# SparkFun_IoT_RedBoard-ESP32.net
KiCad netlist of a schematic drawn in EAGLE
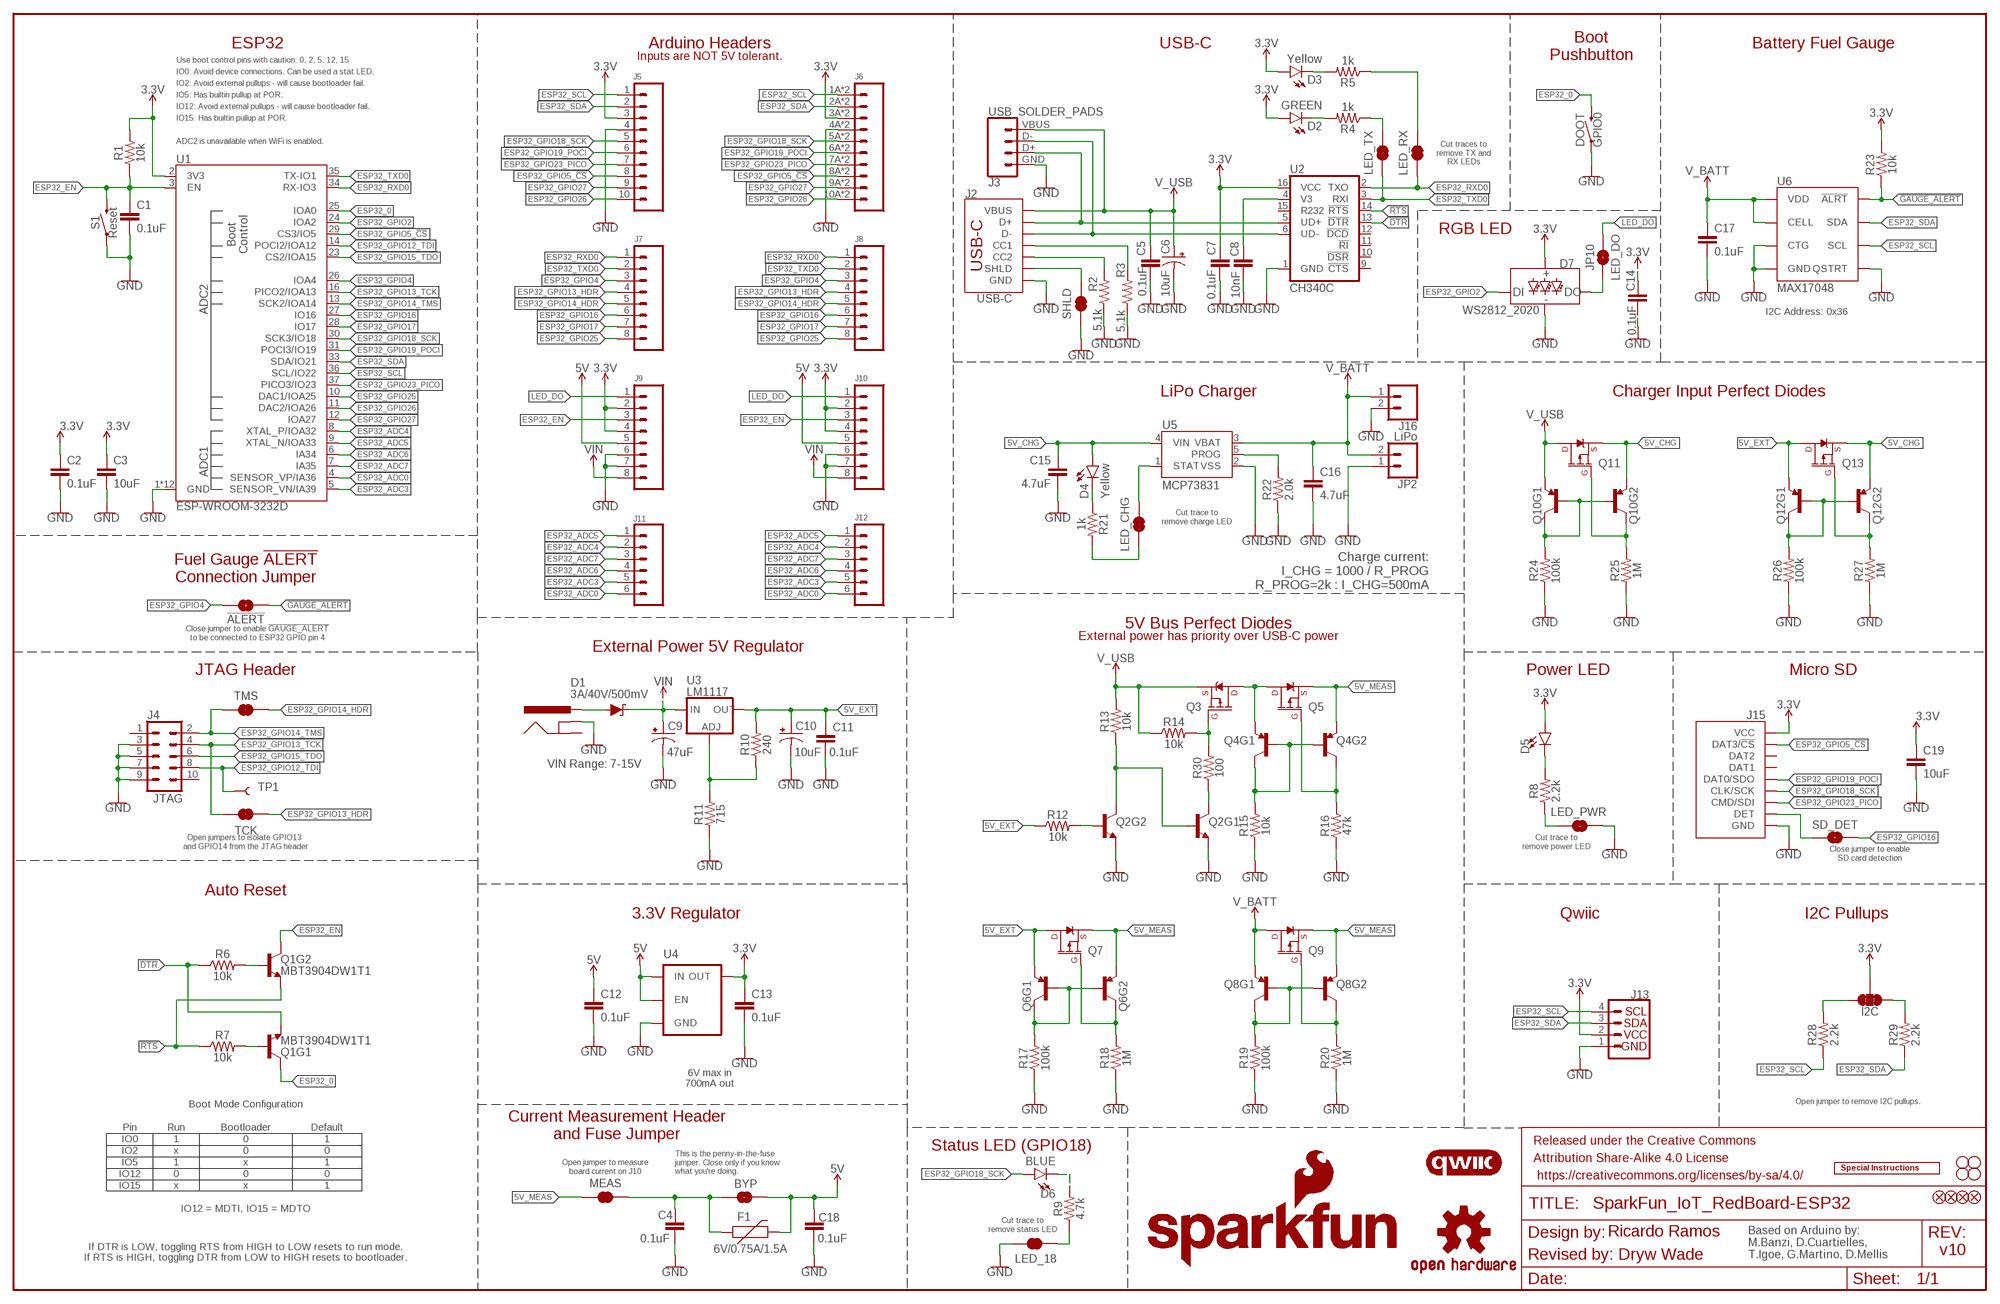
[diagram p0: schematic, sheet 1]

(export (version "E")
  (design (tool "Eeschema 10.0.6"))
  (components
    (comp (ref "!ALERT!")
      (value "JUMPER-SMT_2_NO_SILK")
      (footprint "eagle-import:SMT-JUMPER_2_NO_SILK")
      (libsource (lib "eagle-import") (part "JUMPER-SMT_2_NO_SILK"))
    )
    (comp (ref "BYP")
      (value "JUMPER-SMT_2_NO_SILK")
      (footprint "eagle-import:SMT-JUMPER_2_NO_SILK")
      (libsource (lib "eagle-import") (part "JUMPER-SMT_2_NO_SILK"))
    )
    (comp (ref "C1")
      (value "0.1uF")
      (footprint "eagle-import:0603")
      (libsource (lib "eagle-import") (part "0.1UF-0603-25V-(+80/-20%)"))
    )
    (comp (ref "C2")
      (value "0.1uF")
      (footprint "eagle-import:0603")
      (libsource (lib "eagle-import") (part "0.1UF-0603-25V-(+80/-20%)"))
    )
    (comp (ref "C3")
      (value "10uF")
      (footprint "eagle-import:0603")
      (libsource (lib "eagle-import") (part "10UF-0603-6.3V-20%"))
    )
    (comp (ref "C4")
      (value "0.1uF")
      (footprint "eagle-import:0603")
      (libsource (lib "eagle-import") (part "0.1UF-0603-25V-(+80/-20%)"))
    )
    (comp (ref "C5")
      (value "0.1uF")
      (footprint "eagle-import:0603")
      (libsource (lib "eagle-import") (part "0.1UF-0603-25V-(+80/-20%)"))
    )
    (comp (ref "C6")
      (value "10uF")
      (footprint "eagle-import:EIA3216")
      (libsource (lib "eagle-import") (part "10UF-POLAR-EIA3216-16V-10%(TANT)"))
    )
    (comp (ref "C7")
      (value "0.1uF")
      (footprint "eagle-import:0603")
      (libsource (lib "eagle-import") (part "0.1UF-0603-25V-(+80/-20%)"))
    )
    (comp (ref "C8")
      (value "10nF")
      (footprint "eagle-import:0603")
      (libsource (lib "eagle-import") (part "10NF-0603-50V-10%"))
    )
    (comp (ref "C9")
      (value "47uF")
      (footprint "eagle-import:PANASONIC_D")
      (libsource (lib "eagle-import") (part "47UF-POLAR-PANASONIC_D-35V-20%"))
    )
    (comp (ref "C10")
      (value "10uF")
      (footprint "eagle-import:EIA3216")
      (libsource (lib "eagle-import") (part "10UF-POLAR-EIA3216-16V-10%(TANT)"))
    )
    (comp (ref "C11")
      (value "0.1uF")
      (footprint "eagle-import:0603")
      (libsource (lib "eagle-import") (part "0.1UF-0603-25V-(+80/-20%)"))
    )
    (comp (ref "C12")
      (value "0.1uF")
      (footprint "eagle-import:0603")
      (libsource (lib "eagle-import") (part "0.1UF-0603-25V-(+80/-20%)"))
    )
    (comp (ref "C13")
      (value "0.1uF")
      (footprint "eagle-import:0603")
      (libsource (lib "eagle-import") (part "0.1UF-0603-25V-(+80/-20%)"))
    )
    (comp (ref "C14")
      (value "0.1uF")
      (footprint "eagle-import:0603")
      (libsource (lib "eagle-import") (part "0.1UF-0603-25V-(+80/-20%)"))
    )
    (comp (ref "C15")
      (value "4.7uF")
      (footprint "eagle-import:0603")
      (libsource (lib "eagle-import") (part "4.7UF-0603-35V-(20%)"))
    )
    (comp (ref "C16")
      (value "4.7uF")
      (footprint "eagle-import:0603")
      (libsource (lib "eagle-import") (part "4.7UF-0603-35V-(20%)"))
    )
    (comp (ref "C17")
      (value "0.1uF")
      (footprint "eagle-import:0603")
      (libsource (lib "eagle-import") (part "0.1UF-0603-25V-(+80/-20%)"))
    )
    (comp (ref "C18")
      (value "0.1uF")
      (footprint "eagle-import:0603")
      (libsource (lib "eagle-import") (part "0.1UF-0603-25V-(+80/-20%)"))
    )
    (comp (ref "C19")
      (value "10uF")
      (footprint "eagle-import:0603")
      (libsource (lib "eagle-import") (part "10UF-0603-6.3V-20%"))
    )
    (comp (ref "D1")
      (value "3A/40V/500mV")
      (footprint "eagle-import:SMA-DIODE")
      (libsource (lib "eagle-import") (part "DIODE-SCHOTTKY-B340A"))
    )
    (comp (ref "D2")
      (value "GREEN")
      (footprint "eagle-import:LED-1206")
      (libsource (lib "eagle-import") (part "LED-GREEN1206"))
    )
    (comp (ref "D3")
      (value "Yellow")
      (footprint "eagle-import:LED-1206")
      (libsource (lib "eagle-import") (part "LED-YELLOWLILYPAD"))
    )
    (comp (ref "D4")
      (value "Yellow")
      (footprint "eagle-import:LED-1206")
      (libsource (lib "eagle-import") (part "LED-YELLOWLILYPAD"))
    )
    (comp (ref "D5")
      (value "RED")
      (footprint "eagle-import:LED-1206")
      (libsource (lib "eagle-import") (part "LED-RED1206"))
    )
    (comp (ref "D6")
      (value "BLUE")
      (footprint "eagle-import:LED-1206")
      (libsource (lib "eagle-import") (part "LED-BLUE1206"))
    )
    (comp (ref "D7")
      (value "WS2812_2020")
      (footprint "eagle-import:WS2812-2020")
      (libsource (lib "eagle-import") (part "WS2812_2020"))
    )
    (comp (ref "DOOT")
      (value "GPIO0")
      (footprint "eagle-import:TACTILE_SWITCH_SMD_5.2MM")
      (libsource (lib "eagle-import") (part "MOMENTARY-SWITCH-SPST-SMD-5.2-TALL-REDUNDANT"))
    )
    (comp (ref "F1")
      (value "6V/0.75A/1.5A")
      (footprint "eagle-import:1206")
      (libsource (lib "eagle-import") (part "PPTC_0.75A"))
    )
    (comp (ref "FRAME1")
      (value "FRAME-LEDGER")
      (footprint "eagle-import:CREATIVE_COMMONS")
      (libsource (lib "eagle-import") (part "FRAME-LEDGER"))
    )
    (comp (ref "I2C")
      (value "JUMPER-SMT_3_2-NC_TRACE_SILK")
      (footprint "eagle-import:SMT-JUMPER_3_2-NC_TRACE_SILK")
      (libsource (lib "eagle-import") (part "JUMPER-SMT_3_2-NC_TRACE_SILK"))
    )
    (comp (ref "J1")
      (value "5.5x2.1mm Barrel")
      (footprint "eagle-import:POWER_JACK_SMD")
      (fields (field (name "PROD_ID") "CONN-08106"))
      (libsource (lib "eagle-import") (part "POWER_JACKSMD"))
    )
    (comp (ref "J2")
      (value "USB-C")
      (footprint "eagle-import:USB-C-16P-4LAYER-ISOLATED")
      (libsource (lib "eagle-import") (part "USB_C_4-LAYER-ISOLATED"))
    )
    (comp (ref "J3")
      (value "USB_SOLDER_PADS")
      (footprint "eagle-import:USB-SOLDER-PADS")
      (libsource (lib "eagle-import") (part "USB_SOLDER_PADS"))
    )
    (comp (ref "J4")
      (value "CONN_05X20.05_IN_PTH_SILK")
      (footprint "eagle-import:2X5_PTH_SILK_.05")
      (libsource (lib "eagle-import") (part "CONN_05X20.05_IN_PTH_SILK"))
    )
    (comp (ref "J5")
      (value "M10NO_SILK")
      (footprint "eagle-import:1X10_NO_SILK")
      (libsource (lib "eagle-import") (part "CONN_10NO_SILK_PTH_FEMALE"))
    )
    (comp (ref "J6")
      (value "CONN_10SMD_COMBO-FEMALE")
      (footprint "eagle-import:1X10_SMD_COMBINED")
      (fields (field (name "PROD_ID") "CONN-11219"))
      (libsource (lib "eagle-import") (part "CONN_10SMD_COMBO-FEMALE"))
    )
    (comp (ref "J7")
      (value "CONN_08NO_SILK_FEMALE_PTH")
      (footprint "eagle-import:1X08_NO_SILK")
      (libsource (lib "eagle-import") (part "CONN_08NO_SILK_FEMALE_PTH"))
    )
    (comp (ref "J8")
      (value "CONN_08SMD-COMBO-FEMALE")
      (footprint "eagle-import:1X08_SMD_COMBINED")
      (fields (field (name "PROD_ID") "CONN-10204"))
      (libsource (lib "eagle-import") (part "CONN_08SMD-COMBO-FEMALE"))
    )
    (comp (ref "J9")
      (value "CONN_08NO_SILK_FEMALE_PTH")
      (footprint "eagle-import:1X08_NO_SILK")
      (libsource (lib "eagle-import") (part "CONN_08NO_SILK_FEMALE_PTH"))
    )
    (comp (ref "J10")
      (value "CONN_08SMD-COMBO-FEMALE")
      (footprint "eagle-import:1X08_SMD_COMBINED")
      (fields (field (name "PROD_ID") "CONN-10204"))
      (libsource (lib "eagle-import") (part "CONN_08SMD-COMBO-FEMALE"))
    )
    (comp (ref "J11")
      (value "CONN_06NO_SILK_FEMALE_PTH")
      (footprint "eagle-import:1X06_NO_SILK")
      (libsource (lib "eagle-import") (part "CONN_06NO_SILK_FEMALE_PTH"))
    )
    (comp (ref "J12")
      (value "CONN_06SMD-STRAIGHT-COMBO-FEMALE")
      (footprint "eagle-import:1X06_SMD_STRAIGHT_COMBO")
      (fields (field (name "PROD_ID") "CONN-10203"))
      (libsource (lib "eagle-import") (part "CONN_06SMD-STRAIGHT-COMBO-FEMALE"))
    )
    (comp (ref "J13")
      (value "QWIIC_RIGHT_ANGLE")
      (footprint "eagle-import:JST04_1MM_RA")
      (libsource (lib "eagle-import") (part "QWIIC_CONNECTORJS-1MM"))
    )
    (comp (ref "J15")
      (value "MICRO-SD-PUSH-PUSH-EXT-PIN")
      (footprint "eagle-import:MICROSD-EXTERNALPIN")
      (libsource (lib "eagle-import") (part "MICRO-SD-PUSH-PUSH-EXT-PIN"))
    )
    (comp (ref "J16")
      (value "CONN_021X02_NO_SILK")
      (footprint "eagle-import:1X02_NO_SILK")
      (libsource (lib "eagle-import") (part "CONN_021X02_NO_SILK"))
    )
    (comp (ref "JP1")
      (value "FIDUCIAL1X2")
      (footprint "eagle-import:FIDUCIAL-1X2")
      (libsource (lib "eagle-import") (part "FIDUCIAL1X2"))
    )
    (comp (ref "JP2")
      (value "LiPo")
      (footprint "eagle-import:JST-2-SMD")
      (libsource (lib "eagle-import") (part "CONN_02-JST-2MM-SMT"))
    )
    (comp (ref "JP3")
      (value "STAND-OFF")
      (footprint "eagle-import:STAND-OFF")
      (libsource (lib "eagle-import") (part "STAND-OFF"))
    )
    (comp (ref "JP4")
      (value "STAND-OFF")
      (footprint "eagle-import:STAND-OFF")
      (libsource (lib "eagle-import") (part "STAND-OFF"))
    )
    (comp (ref "JP5")
      (value "STAND-OFF")
      (footprint "eagle-import:STAND-OFF")
      (libsource (lib "eagle-import") (part "STAND-OFF"))
    )
    (comp (ref "JP6")
      (value "STAND-OFF")
      (footprint "eagle-import:STAND-OFF")
      (libsource (lib "eagle-import") (part "STAND-OFF"))
    )
    (comp (ref "JP7")
      (value "FIDUCIAL1X2")
      (footprint "eagle-import:FIDUCIAL-1X2")
      (libsource (lib "eagle-import") (part "FIDUCIAL1X2"))
    )
    (comp (ref "JP8")
      (value "FIDUCIAL1X2")
      (footprint "eagle-import:FIDUCIAL-1X2")
      (libsource (lib "eagle-import") (part "FIDUCIAL1X2"))
    )
    (comp (ref "JP9")
      (value "FIDUCIAL1X2")
      (footprint "eagle-import:FIDUCIAL-1X2")
      (libsource (lib "eagle-import") (part "FIDUCIAL1X2"))
    )
    (comp (ref "JP10")
      (value "LED_DO")
      (footprint "eagle-import:SMT-JUMPER_2_NO_SILK")
      (libsource (lib "eagle-import") (part "JUMPER-SMT_2_NO_SILK"))
    )
    (comp (ref "LED_18")
      (value "JUMPER-SMT_2_NC_TRACE_SILK")
      (footprint "eagle-import:SMT-JUMPER_2_NC_TRACE_SILK")
      (libsource (lib "eagle-import") (part "JUMPER-SMT_2_NC_TRACE_SILK"))
    )
    (comp (ref "LED_CHG")
      (value "JUMPER-SMT_2_NC_TRACE_SILK")
      (footprint "eagle-import:SMT-JUMPER_2_NC_TRACE_SILK")
      (libsource (lib "eagle-import") (part "JUMPER-SMT_2_NC_TRACE_SILK"))
    )
    (comp (ref "LED_PWR")
      (value "JUMPER-SMT_2_NC_TRACE_SILK")
      (footprint "eagle-import:SMT-JUMPER_2_NC_TRACE_SILK")
      (libsource (lib "eagle-import") (part "JUMPER-SMT_2_NC_TRACE_SILK"))
    )
    (comp (ref "LED_RX")
      (value "JUMPER-SMT_2_NC_TRACE_SILK")
      (footprint "eagle-import:SMT-JUMPER_2_NC_TRACE_SILK")
      (libsource (lib "eagle-import") (part "JUMPER-SMT_2_NC_TRACE_SILK"))
    )
    (comp (ref "LED_TX")
      (value "JUMPER-SMT_2_NC_TRACE_SILK")
      (footprint "eagle-import:SMT-JUMPER_2_NC_TRACE_SILK")
      (libsource (lib "eagle-import") (part "JUMPER-SMT_2_NC_TRACE_SILK"))
    )
    (comp (ref "LOGO1")
      (value "SFE_LOGO_NAME.1_INCH")
      (footprint "eagle-import:SFE_LOGO_NAME_.1")
      (libsource (lib "eagle-import") (part "SFE_LOGO_NAME.1_INCH"))
    )
    (comp (ref "LOGO2")
      (value "QWIIC_LOGO_5MM")
      (footprint "eagle-import:QWIIC_5MM")
      (libsource (lib "eagle-import") (part "QWIIC_LOGO_5MM"))
    )
    (comp (ref "LOGO3")
      (value "OSHW-LOGOMINI")
      (footprint "eagle-import:OSHW-LOGO-MINI")
      (libsource (lib "eagle-import") (part "OSHW-LOGOMINI"))
    )
    (comp (ref "LOGO5")
      (value "SPECIAL_INSTRUCTIONS-ORDERING")
      (footprint "eagle-import:ORDERING_INSTRUCTIONS")
      (libsource (lib "eagle-import") (part "SPECIAL_INSTRUCTIONS-ORDERING"))
    )
    (comp (ref "LOGO6")
      (value "SFE_LOGO_NAME_FLAME.2_INCH")
      (footprint "eagle-import:SFE_LOGO_NAME_FLAME_.2")
      (libsource (lib "eagle-import") (part "SFE_LOGO_NAME_FLAME.2_INCH"))
    )
    (comp (ref "MEAS")
      (value "JUMPER-COMBO_2_NC_TRACE")
      (footprint "eagle-import:COMBO-JUMPER_2_NC_TRACE")
      (libsource (lib "eagle-import") (part "JUMPER-COMBO_2_NC_TRACE"))
    )
    (comp (ref "Q1")
      (value "MBT3904DW1T1")
      (footprint "eagle-import:SC70-6")
      (libsource (lib "eagle-import") (part "TRANS_NPN_DUAL-MBT3904DW1T1"))
    )
    (comp (ref "Q2")
      (value "TRANS_NPN_DUAL-MBT3904DW1T1")
      (footprint "eagle-import:SC70-6")
      (libsource (lib "eagle-import") (part "TRANS_NPN_DUAL-MBT3904DW1T1"))
    )
    (comp (ref "Q3")
      (value "20V/4.2A/52mΩ/1.4W")
      (footprint "eagle-import:SOT23-3")
      (libsource (lib "eagle-import") (part "MOSFET_PCH-DMG2305UX-7"))
    )
    (comp (ref "Q4")
      (value "TRANS_PNP_DUALSOT-363")
      (footprint "eagle-import:SOT363_PHILIPS")
      (libsource (lib "eagle-import") (part "TRANS_PNP_DUALSOT-363"))
    )
    (comp (ref "Q5")
      (value "20V/4.2A/52mΩ/1.4W")
      (footprint "eagle-import:SOT23-3")
      (libsource (lib "eagle-import") (part "MOSFET_PCH-DMG2305UX-7"))
    )
    (comp (ref "Q6")
      (value "TRANS_PNP_DUALSOT-363")
      (footprint "eagle-import:SOT363_PHILIPS")
      (libsource (lib "eagle-import") (part "TRANS_PNP_DUALSOT-363"))
    )
    (comp (ref "Q7")
      (value "20V/4.2A/52mΩ/1.4W")
      (footprint "eagle-import:SOT23-3")
      (libsource (lib "eagle-import") (part "MOSFET_PCH-DMG2305UX-7"))
    )
    (comp (ref "Q8")
      (value "TRANS_PNP_DUALSOT-363")
      (footprint "eagle-import:SOT363_PHILIPS")
      (libsource (lib "eagle-import") (part "TRANS_PNP_DUALSOT-363"))
    )
    (comp (ref "Q9")
      (value "20V/4.2A/52mΩ/1.4W")
      (footprint "eagle-import:SOT23-3")
      (libsource (lib "eagle-import") (part "MOSFET_PCH-DMG2305UX-7"))
    )
    (comp (ref "Q10")
      (value "TRANS_PNP_DUALSOT-363")
      (footprint "eagle-import:SOT363_PHILIPS")
      (libsource (lib "eagle-import") (part "TRANS_PNP_DUALSOT-363"))
    )
    (comp (ref "Q11")
      (value "20V/4.2A/52mΩ/1.4W")
      (footprint "eagle-import:SOT23-3")
      (libsource (lib "eagle-import") (part "MOSFET_PCH-DMG2305UX-7"))
    )
    (comp (ref "Q12")
      (value "TRANS_PNP_DUALSOT-363")
      (footprint "eagle-import:SOT363_PHILIPS")
      (libsource (lib "eagle-import") (part "TRANS_PNP_DUALSOT-363"))
    )
    (comp (ref "Q13")
      (value "20V/4.2A/52mΩ/1.4W")
      (footprint "eagle-import:SOT23-3")
      (libsource (lib "eagle-import") (part "MOSFET_PCH-DMG2305UX-7"))
    )
    (comp (ref "R1")
      (value "10k")
      (footprint "eagle-import:0603")
      (libsource (lib "eagle-import") (part "10KOHM-0603-1/10W-1%"))
    )
    (comp (ref "R2")
      (value "5.1k")
      (footprint "eagle-import:0603")
      (libsource (lib "eagle-import") (part "5.1KOHM5.1KOHM-0603-1/10W-1%"))
    )
    (comp (ref "R3")
      (value "5.1k")
      (footprint "eagle-import:0603")
      (libsource (lib "eagle-import") (part "5.1KOHM5.1KOHM-0603-1/10W-1%"))
    )
    (comp (ref "R4")
      (value "1k")
      (footprint "eagle-import:0603")
      (libsource (lib "eagle-import") (part "1KOHM-0603-1/10W-1%"))
    )
    (comp (ref "R5")
      (value "1k")
      (footprint "eagle-import:0603")
      (libsource (lib "eagle-import") (part "1KOHM-0603-1/10W-1%"))
    )
    (comp (ref "R6")
      (value "10k")
      (footprint "eagle-import:0603")
      (libsource (lib "eagle-import") (part "10KOHM-0603-1/10W-1%"))
    )
    (comp (ref "R7")
      (value "10k")
      (footprint "eagle-import:0603")
      (libsource (lib "eagle-import") (part "10KOHM-0603-1/10W-1%"))
    )
    (comp (ref "R8")
      (value "2.2k")
      (footprint "eagle-import:0603")
      (libsource (lib "eagle-import") (part "2.2KOHM-0603-1/10W-1%"))
    )
    (comp (ref "R9")
      (value "4.7k")
      (footprint "eagle-import:0603")
      (libsource (lib "eagle-import") (part "4.7KOHM-0603-1/10W-1%"))
    )
    (comp (ref "R10")
      (value "240")
      (footprint "eagle-import:0603")
      (libsource (lib "eagle-import") (part "240OHM-0603-1/10W-1%"))
    )
    (comp (ref "R11")
      (value "715")
      (footprint "eagle-import:0603")
      (libsource (lib "eagle-import") (part "715OHM-0603-1/10W-1%"))
    )
    (comp (ref "R12")
      (value "10k")
      (footprint "eagle-import:0603")
      (libsource (lib "eagle-import") (part "10KOHM-0603-1/10W-1%"))
    )
    (comp (ref "R13")
      (value "10k")
      (footprint "eagle-import:0603")
      (libsource (lib "eagle-import") (part "10KOHM-0603-1/10W-1%"))
    )
    (comp (ref "R14")
      (value "10k")
      (footprint "eagle-import:0603")
      (libsource (lib "eagle-import") (part "10KOHM-0603-1/10W-1%"))
    )
    (comp (ref "R15")
      (value "10k")
      (footprint "eagle-import:0603")
      (libsource (lib "eagle-import") (part "10KOHM-0603-1/10W-1%"))
    )
    (comp (ref "R16")
      (value "47k")
      (footprint "eagle-import:0603")
      (libsource (lib "eagle-import") (part "47KOHM-0603-1/10W-1%"))
    )
    (comp (ref "R17")
      (value "100k")
      (footprint "eagle-import:0603")
      (libsource (lib "eagle-import") (part "100KOHM-0603-1/10W-1%"))
    )
    (comp (ref "R18")
      (value "1M")
      (footprint "eagle-import:0603")
      (libsource (lib "eagle-import") (part "1MOHM-0603-1/4W-5%"))
    )
    (comp (ref "R19")
      (value "100k")
      (footprint "eagle-import:0603")
      (libsource (lib "eagle-import") (part "100KOHM-0603-1/10W-1%"))
    )
    (comp (ref "R20")
      (value "1M")
      (footprint "eagle-import:0603")
      (libsource (lib "eagle-import") (part "1MOHM-0603-1/4W-5%"))
    )
    (comp (ref "R21")
      (value "1k")
      (footprint "eagle-import:0603")
      (libsource (lib "eagle-import") (part "1KOHM-0603-1/10W-1%"))
    )
    (comp (ref "R22")
      (value "2.0k")
      (footprint "eagle-import:0603")
      (libsource (lib "eagle-import") (part "2.0KOHM-0603-1/10W-5%"))
    )
    (comp (ref "R23")
      (value "10k")
      (footprint "eagle-import:0603")
      (libsource (lib "eagle-import") (part "10KOHM-0603-1/10W-1%"))
    )
    (comp (ref "R24")
      (value "100k")
      (footprint "eagle-import:0603")
      (libsource (lib "eagle-import") (part "100KOHM-0603-1/10W-1%"))
    )
    (comp (ref "R25")
      (value "1M")
      (footprint "eagle-import:0603")
      (libsource (lib "eagle-import") (part "1MOHM-0603-1/4W-5%"))
    )
    (comp (ref "R26")
      (value "100k")
      (footprint "eagle-import:0603")
      (libsource (lib "eagle-import") (part "100KOHM-0603-1/10W-1%"))
    )
    (comp (ref "R27")
      (value "1M")
      (footprint "eagle-import:0603")
      (libsource (lib "eagle-import") (part "1MOHM-0603-1/4W-5%"))
    )
    (comp (ref "R28")
      (value "2.2k")
      (footprint "eagle-import:0603")
      (libsource (lib "eagle-import") (part "2.2KOHM-0603-1/10W-1%"))
    )
    (comp (ref "R29")
      (value "2.2k")
      (footprint "eagle-import:0603")
      (libsource (lib "eagle-import") (part "2.2KOHM-0603-1/10W-1%"))
    )
    (comp (ref "R30")
      (value "100")
      (footprint "eagle-import:0603")
      (libsource (lib "eagle-import") (part "100OHM-0603-1/10W-1%"))
    )
    (comp (ref "S1")
      (value "Reset")
      (footprint "eagle-import:TACTILE_SWITCH_SMD_5.2MM")
      (libsource (lib "eagle-import") (part "MOMENTARY-SWITCH-SPST-SMD-5.2-TALL-REDUNDANT"))
    )
    (comp (ref "SD_DET")
      (value "SD_DET")
      (footprint "eagle-import:SMT-JUMPER_2_NO_SILK")
      (libsource (lib "eagle-import") (part "JUMPER-SMT_2_NO_SILK"))
    )
    (comp (ref "SHLD")
      (value "SHLD")
      (footprint "eagle-import:SMT-JUMPER_2_NC_TRACE_SILK")
      (libsource (lib "eagle-import") (part "JUMPER-SMT_2_NC_TRACE_SILK"))
    )
    (comp (ref "TCK")
      (value "JUMPER-SMT_2_NC_TRACE_SILK")
      (footprint "eagle-import:SMT-JUMPER_2_NC_TRACE_SILK")
      (libsource (lib "eagle-import") (part "JUMPER-SMT_2_NC_TRACE_SILK"))
    )
    (comp (ref "TMS")
      (value "JUMPER-SMT_2_NC_TRACE_SILK")
      (footprint "eagle-import:SMT-JUMPER_2_NC_TRACE_SILK")
      (libsource (lib "eagle-import") (part "JUMPER-SMT_2_NC_TRACE_SILK"))
    )
    (comp (ref "TP1")
      (value "TEST-POINT3")
      (footprint "eagle-import:PAD.03X.03")
      (libsource (lib "eagle-import") (part "TEST-POINT3"))
    )
    (comp (ref "U1")
      (value "ESP-WROOM-3232D")
      (footprint "eagle-import:ESP-WROOM-32D")
      (libsource (lib "eagle-import") (part "ESP-WROOM-3232D"))
    )
    (comp (ref "U2")
      (value "CH340C")
      (footprint "eagle-import:SO016")
      (libsource (lib "eagle-import") (part "CH340C"))
    )
    (comp (ref "U3")
      (value "LM1117")
      (footprint "eagle-import:SOT223")
      (libsource (lib "eagle-import") (part "V_REG_LM1117SOT223"))
    )
    (comp (ref "U4")
      (value "XC6222B331MR-G")
      (footprint "eagle-import:SOT23-5")
      (libsource (lib "eagle-import") (part "XC6222B331MR-G"))
    )
    (comp (ref "U5")
      (value "MCP73831")
      (footprint "eagle-import:SOT23-5")
      (libsource (lib "eagle-import") (part "MCP73831"))
    )
    (comp (ref "U6")
      (value "MAX17048")
      (footprint "eagle-import:DFN-8")
      (libsource (lib "eagle-import") (part "MAX17048DFN8"))
    )
  )
  (nets
    (net (code "1") (name "/ESP32_GPIO5_~{CS}") (class "Default")
      (node (ref "J15") (pin "2") (pinfunction "DAT3/~{CS}_2") (pintype "bidirectional"))
      (node (ref "J5") (pin "8") (pinfunction "8_8") (pintype "passive"))
      (node (ref "J6") (pin "8A") (pinfunction "8_8A") (pintype "passive"))
      (node (ref "J6") (pin "8B") (pinfunction "8_8B") (pintype "passive"))
      (node (ref "U1") (pin "29") (pinfunction "CS3/IO5_29") (pintype "bidirectional"))
    )
    (net (code "2") (name "/~{DTR}") (class "Default")
      (node (ref "Q1") (pin "4") (pinfunction "E_4") (pintype "passive"))
      (node (ref "R6") (pin "1") (pinfunction "1_1") (pintype "passive"))
      (node (ref "U2") (pin "13") (pinfunction "~{DTR}_13") (pintype "bidirectional"))
    )
    (net (code "3") (name "/~{GAUGE_ALERT}") (class "Default")
      (node (ref "!ALERT!") (pin "1") (pinfunction "1_1") (pintype "passive"))
      (node (ref "R23") (pin "1") (pinfunction "1_1") (pintype "passive"))
      (node (ref "U6") (pin "5") (pinfunction "~{ALRT}_5") (pintype "bidirectional"))
    )
    (net (code "4") (name "/~{RTS}") (class "Default")
      (node (ref "Q1") (pin "1") (pinfunction "E_1") (pintype "passive"))
      (node (ref "R7") (pin "1") (pinfunction "1_1") (pintype "passive"))
      (node (ref "U2") (pin "14") (pinfunction "~{RTS}_14") (pintype "bidirectional"))
    )
    (net (code "5") (name "3.3V") (class "Default")
      (node (ref "C13") (pin "1") (pinfunction "1_1") (pintype "passive"))
      (node (ref "C14") (pin "1") (pinfunction "1_1") (pintype "passive"))
      (node (ref "C19") (pin "1") (pinfunction "1_1") (pintype "passive"))
      (node (ref "C2") (pin "1") (pinfunction "1_1") (pintype "passive"))
      (node (ref "C3") (pin "1") (pinfunction "1_1") (pintype "passive"))
      (node (ref "C7") (pin "1") (pinfunction "1_1") (pintype "passive"))
      (node (ref "D2") (pin "A") (pinfunction "A_A") (pintype "passive"))
      (node (ref "D3") (pin "A") (pinfunction "A_A") (pintype "passive"))
      (node (ref "D5") (pin "A") (pinfunction "A_A") (pintype "passive"))
      (node (ref "D7") (pin "VCC") (pinfunction "VCC_VCC") (pintype "bidirectional"))
      (node (ref "I2C") (pin "2") (pinfunction "2_2") (pintype "passive"))
      (node (ref "J10") (pin "2") (pinfunction "2_2") (pintype "passive"))
      (node (ref "J10") (pin "4") (pinfunction "4_4") (pintype "passive"))
      (node (ref "J13") (pin "2") (pinfunction "2_2") (pintype "power_in"))
      (node (ref "J15") (pin "4") (pinfunction "VCC_4") (pintype "bidirectional"))
      (node (ref "J5") (pin "3") (pinfunction "3_3") (pintype "passive"))
      (node (ref "J6") (pin "3A") (pinfunction "3_3A") (pintype "passive"))
      (node (ref "J6") (pin "3B") (pinfunction "3_3B") (pintype "passive"))
      (node (ref "J9") (pin "2") (pinfunction "2_2") (pintype "passive"))
      (node (ref "J9") (pin "4") (pinfunction "4_4") (pintype "passive"))
      (node (ref "R1") (pin "2") (pinfunction "2_2") (pintype "passive"))
      (node (ref "R23") (pin "2") (pinfunction "2_2") (pintype "passive"))
      (node (ref "U1") (pin "2") (pinfunction "3V3_2") (pintype "bidirectional"))
      (node (ref "U2") (pin "16") (pinfunction "VCC_16") (pintype "bidirectional"))
      (node (ref "U4") (pin "5") (pinfunction "OUT_5") (pintype "passive"))
    )
    (net (code "6") (name "5V") (class "Default")
      (node (ref "BYP") (pin "2") (pinfunction "2_2") (pintype "passive"))
      (node (ref "C12") (pin "1") (pinfunction "1_1") (pintype "passive"))
      (node (ref "C18") (pin "1") (pinfunction "1_1") (pintype "passive"))
      (node (ref "F1") (pin "2") (pinfunction "2_2") (pintype "bidirectional"))
      (node (ref "J10") (pin "5") (pinfunction "5_5") (pintype "passive"))
      (node (ref "J9") (pin "5") (pinfunction "5_5") (pintype "passive"))
      (node (ref "U4") (pin "1") (pinfunction "IN_1") (pintype "input"))
      (node (ref "U4") (pin "3") (pinfunction "EN_3") (pintype "input"))
    )
    (net (code "7") (name "5V_CHG") (class "Default")
      (node (ref "C15") (pin "1") (pinfunction "1_1") (pintype "passive"))
      (node (ref "D4") (pin "A") (pinfunction "A_A") (pintype "passive"))
      (node (ref "Q10") (pin "4") (pinfunction "E_4") (pintype "passive"))
      (node (ref "Q11") (pin "2") (pinfunction "S_2") (pintype "bidirectional"))
      (node (ref "Q12") (pin "4") (pinfunction "E_4") (pintype "passive"))
      (node (ref "Q13") (pin "2") (pinfunction "S_2") (pintype "bidirectional"))
      (node (ref "U5") (pin "4") (pinfunction "VIN_4") (pintype "power_in"))
    )
    (net (code "8") (name "5V_EXT") (class "Default")
      (node (ref "C10") (pin "+") (pinfunction "+_+") (pintype "passive"))
      (node (ref "C11") (pin "1") (pinfunction "1_1") (pintype "passive"))
      (node (ref "Q12") (pin "1") (pinfunction "E_1") (pintype "passive"))
      (node (ref "Q13") (pin "3") (pinfunction "D_3") (pintype "bidirectional"))
      (node (ref "Q6") (pin "1") (pinfunction "E_1") (pintype "passive"))
      (node (ref "Q7") (pin "3") (pinfunction "D_3") (pintype "bidirectional"))
      (node (ref "R10") (pin "2") (pinfunction "2_2") (pintype "passive"))
      (node (ref "R12") (pin "1") (pinfunction "1_1") (pintype "passive"))
      (node (ref "U3") (pin "2") (pinfunction "OUT_2") (pintype "output"))
      (node (ref "U3") (pin "4") (pinfunction "OUT_4") (pintype "output"))
    )
    (net (code "9") (name "5V_MEAS") (class "Default")
      (node (ref "MEAS") (pin "1") (pinfunction "1_1") (pintype "passive"))
      (node (ref "MEAS") (pin "3") (pinfunction "1_3") (pintype "passive"))
      (node (ref "Q4") (pin "4") (pinfunction "E_4") (pintype "passive"))
      (node (ref "Q5") (pin "2") (pinfunction "S_2") (pintype "bidirectional"))
      (node (ref "Q6") (pin "4") (pinfunction "E_4") (pintype "passive"))
      (node (ref "Q7") (pin "2") (pinfunction "S_2") (pintype "bidirectional"))
      (node (ref "Q8") (pin "4") (pinfunction "E_4") (pintype "passive"))
      (node (ref "Q9") (pin "2") (pinfunction "S_2") (pintype "bidirectional"))
    )
    (net (code "10") (name "ESP32_0") (class "Default")
      (node (ref "DOOT") (pin "3") (pinfunction "2_3") (pintype "passive"))
      (node (ref "DOOT") (pin "4") (pinfunction "2_4") (pintype "passive"))
      (node (ref "Q1") (pin "3") (pinfunction "C_3") (pintype "passive"))
      (node (ref "U1") (pin "25") (pinfunction "IOA0_25") (pintype "bidirectional"))
    )
    (net (code "11") (name "ESP32_ADC0") (class "Default")
      (node (ref "J11") (pin "6") (pinfunction "6_6") (pintype "passive"))
      (node (ref "J12") (pin "6") (pinfunction "6_6") (pintype "passive"))
      (node (ref "U1") (pin "4") (pinfunction "SENSOR_VP/IA36_4") (pintype "bidirectional"))
    )
    (net (code "12") (name "ESP32_ADC3") (class "Default")
      (node (ref "J11") (pin "5") (pinfunction "5_5") (pintype "passive"))
      (node (ref "J12") (pin "5") (pinfunction "5_5") (pintype "passive"))
      (node (ref "U1") (pin "5") (pinfunction "SENSOR_VN/IA39_5") (pintype "bidirectional"))
    )
    (net (code "13") (name "ESP32_ADC4") (class "Default")
      (node (ref "J11") (pin "2") (pinfunction "2_2") (pintype "passive"))
      (node (ref "J12") (pin "2") (pinfunction "2_2") (pintype "passive"))
      (node (ref "U1") (pin "8") (pinfunction "XTAL_P/IOA32_8") (pintype "bidirectional"))
    )
    (net (code "14") (name "ESP32_ADC5") (class "Default")
      (node (ref "J11") (pin "1") (pinfunction "1_1") (pintype "passive"))
      (node (ref "J12") (pin "1") (pinfunction "1_1") (pintype "passive"))
      (node (ref "U1") (pin "9") (pinfunction "XTAL_N/IOA33_9") (pintype "bidirectional"))
    )
    (net (code "15") (name "ESP32_ADC6") (class "Default")
      (node (ref "J11") (pin "4") (pinfunction "4_4") (pintype "passive"))
      (node (ref "J12") (pin "4") (pinfunction "4_4") (pintype "passive"))
      (node (ref "U1") (pin "6") (pinfunction "IA34_6") (pintype "bidirectional"))
    )
    (net (code "16") (name "ESP32_ADC7") (class "Default")
      (node (ref "J11") (pin "3") (pinfunction "3_3") (pintype "passive"))
      (node (ref "J12") (pin "3") (pinfunction "3_3") (pintype "passive"))
      (node (ref "U1") (pin "7") (pinfunction "IA35_7") (pintype "bidirectional"))
    )
    (net (code "17") (name "ESP32_EN") (class "Default")
      (node (ref "C1") (pin "1") (pinfunction "1_1") (pintype "passive"))
      (node (ref "J10") (pin "3") (pinfunction "3_3") (pintype "passive"))
      (node (ref "J9") (pin "3") (pinfunction "3_3") (pintype "passive"))
      (node (ref "Q1") (pin "6") (pinfunction "C_6") (pintype "passive"))
      (node (ref "R1") (pin "1") (pinfunction "1_1") (pintype "passive"))
      (node (ref "S1") (pin "3") (pinfunction "2_3") (pintype "passive"))
      (node (ref "S1") (pin "4") (pinfunction "2_4") (pintype "passive"))
      (node (ref "U1") (pin "3") (pinfunction "EN_3") (pintype "bidirectional"))
    )
    (net (code "18") (name "ESP32_GPIO2") (class "Default")
      (node (ref "D7") (pin "DI") (pinfunction "DI_DI") (pintype "bidirectional"))
      (node (ref "U1") (pin "24") (pinfunction "IOA2_24") (pintype "bidirectional"))
    )
    (net (code "19") (name "ESP32_GPIO4") (class "Default")
      (node (ref "!ALERT!") (pin "2") (pinfunction "2_2") (pintype "passive"))
      (node (ref "J7") (pin "3") (pinfunction "3_3") (pintype "passive"))
      (node (ref "J8") (pin "3") (pinfunction "3_3") (pintype "passive"))
      (node (ref "U1") (pin "26") (pinfunction "IOA4_26") (pintype "bidirectional"))
    )
    (net (code "20") (name "ESP32_GPIO12_TDI") (class "Default")
      (node (ref "J4") (pin "8") (pinfunction "8_8") (pintype "passive"))
      (node (ref "TP1") (pin "1") (pinfunction "1_1") (pintype "bidirectional"))
      (node (ref "U1") (pin "14") (pinfunction "POCI2/IOA12_14") (pintype "bidirectional"))
    )
    (net (code "21") (name "ESP32_GPIO13_HDR") (class "Default")
      (node (ref "J7") (pin "4") (pinfunction "4_4") (pintype "passive"))
      (node (ref "J8") (pin "4") (pinfunction "4_4") (pintype "passive"))
      (node (ref "TCK") (pin "2") (pinfunction "2_2") (pintype "passive"))
    )
    (net (code "22") (name "ESP32_GPIO13_TCK") (class "Default")
      (node (ref "J4") (pin "4") (pinfunction "4_4") (pintype "passive"))
      (node (ref "TCK") (pin "1") (pinfunction "1_1") (pintype "passive"))
      (node (ref "U1") (pin "16") (pinfunction "PICO2/IOA13_16") (pintype "bidirectional"))
    )
    (net (code "23") (name "ESP32_GPIO14_HDR") (class "Default")
      (node (ref "J7") (pin "5") (pinfunction "5_5") (pintype "passive"))
      (node (ref "J8") (pin "5") (pinfunction "5_5") (pintype "passive"))
      (node (ref "TMS") (pin "2") (pinfunction "2_2") (pintype "passive"))
    )
    (net (code "24") (name "ESP32_GPIO14_TMS") (class "Default")
      (node (ref "J4") (pin "2") (pinfunction "2_2") (pintype "passive"))
      (node (ref "TMS") (pin "1") (pinfunction "1_1") (pintype "passive"))
      (node (ref "U1") (pin "13") (pinfunction "SCK2/IOA14_13") (pintype "bidirectional"))
    )
    (net (code "25") (name "ESP32_GPIO15_TDO") (class "Default")
      (node (ref "J4") (pin "6") (pinfunction "6_6") (pintype "passive"))
      (node (ref "U1") (pin "23") (pinfunction "CS2/IOA15_23") (pintype "bidirectional"))
    )
    (net (code "26") (name "ESP32_GPIO16") (class "Default")
      (node (ref "J7") (pin "6") (pinfunction "6_6") (pintype "passive"))
      (node (ref "J8") (pin "6") (pinfunction "6_6") (pintype "passive"))
      (node (ref "SD_DET") (pin "2") (pinfunction "2_2") (pintype "passive"))
      (node (ref "U1") (pin "27") (pinfunction "IO16_27") (pintype "bidirectional"))
    )
    (net (code "27") (name "ESP32_GPIO17") (class "Default")
      (node (ref "J7") (pin "7") (pinfunction "7_7") (pintype "passive"))
      (node (ref "J8") (pin "7") (pinfunction "7_7") (pintype "passive"))
      (node (ref "U1") (pin "28") (pinfunction "IO17_28") (pintype "bidirectional"))
    )
    (net (code "28") (name "ESP32_GPIO18_SCK") (class "Default")
      (node (ref "D6") (pin "A") (pinfunction "A_A") (pintype "passive"))
      (node (ref "J15") (pin "5") (pinfunction "CLK/SCK_5") (pintype "bidirectional"))
      (node (ref "J5") (pin "5") (pinfunction "5_5") (pintype "passive"))
      (node (ref "J6") (pin "5A") (pinfunction "5_5A") (pintype "passive"))
      (node (ref "J6") (pin "5B") (pinfunction "5_5B") (pintype "passive"))
      (node (ref "U1") (pin "30") (pinfunction "SCK3/IO18_30") (pintype "bidirectional"))
    )
    (net (code "29") (name "ESP32_GPIO19_POCI") (class "Default")
      (node (ref "J15") (pin "7") (pinfunction "DAT0/SDO_7") (pintype "bidirectional"))
      (node (ref "J5") (pin "6") (pinfunction "6_6") (pintype "passive"))
      (node (ref "J6") (pin "6A") (pinfunction "6_6A") (pintype "passive"))
      (node (ref "J6") (pin "6B") (pinfunction "6_6B") (pintype "passive"))
      (node (ref "U1") (pin "31") (pinfunction "POCI3/IO19_31") (pintype "bidirectional"))
    )
    (net (code "30") (name "ESP32_GPIO23_PICO") (class "Default")
      (node (ref "J15") (pin "3") (pinfunction "CMD/SDI_3") (pintype "bidirectional"))
      (node (ref "J5") (pin "7") (pinfunction "7_7") (pintype "passive"))
      (node (ref "J6") (pin "7A") (pinfunction "7_7A") (pintype "passive"))
      (node (ref "J6") (pin "7B") (pinfunction "7_7B") (pintype "passive"))
      (node (ref "U1") (pin "37") (pinfunction "PICO3/IO23_37") (pintype "bidirectional"))
    )
    (net (code "31") (name "ESP32_GPIO25") (class "Default")
      (node (ref "J7") (pin "8") (pinfunction "8_8") (pintype "passive"))
      (node (ref "J8") (pin "8") (pinfunction "8_8") (pintype "passive"))
      (node (ref "U1") (pin "10") (pinfunction "DAC1/IOA25_10") (pintype "bidirectional"))
    )
    (net (code "32") (name "ESP32_GPIO26") (class "Default")
      (node (ref "J5") (pin "10") (pinfunction "10_10") (pintype "passive"))
      (node (ref "J6") (pin "10A") (pinfunction "10_10A") (pintype "passive"))
      (node (ref "J6") (pin "10B") (pinfunction "10_10B") (pintype "passive"))
      (node (ref "U1") (pin "11") (pinfunction "DAC2/IOA26_11") (pintype "bidirectional"))
    )
    (net (code "33") (name "ESP32_GPIO27") (class "Default")
      (node (ref "J5") (pin "9") (pinfunction "9_9") (pintype "passive"))
      (node (ref "J6") (pin "9A") (pinfunction "9_9A") (pintype "passive"))
      (node (ref "J6") (pin "9B") (pinfunction "9_9B") (pintype "passive"))
      (node (ref "U1") (pin "12") (pinfunction "IOA27_12") (pintype "bidirectional"))
    )
    (net (code "34") (name "ESP32_RXD0") (class "Default")
      (node (ref "J7") (pin "1") (pinfunction "1_1") (pintype "passive"))
      (node (ref "J8") (pin "1") (pinfunction "1_1") (pintype "passive"))
      (node (ref "LED_RX") (pin "1") (pinfunction "1_1") (pintype "passive"))
      (node (ref "U1") (pin "34") (pinfunction "RX-IO3_34") (pintype "bidirectional"))
      (node (ref "U2") (pin "2") (pinfunction "TXO_2") (pintype "bidirectional"))
    )
    (net (code "35") (name "ESP32_SCL") (class "Default")
      (node (ref "J13") (pin "4") (pinfunction "4_4") (pintype "passive"))
      (node (ref "J5") (pin "1") (pinfunction "1_1") (pintype "passive"))
      (node (ref "J6") (pin "1A") (pinfunction "1_1A") (pintype "passive"))
      (node (ref "J6") (pin "1B") (pinfunction "1_1B") (pintype "passive"))
      (node (ref "R28") (pin "1") (pinfunction "1_1") (pintype "passive"))
      (node (ref "U1") (pin "36") (pinfunction "SCL/IO22_36") (pintype "bidirectional"))
      (node (ref "U6") (pin "7") (pinfunction "SCL_7") (pintype "output"))
    )
    (net (code "36") (name "ESP32_SDA") (class "Default")
      (node (ref "J13") (pin "3") (pinfunction "3_3") (pintype "passive"))
      (node (ref "J5") (pin "2") (pinfunction "2_2") (pintype "passive"))
      (node (ref "J6") (pin "2A") (pinfunction "2_2A") (pintype "passive"))
      (node (ref "J6") (pin "2B") (pinfunction "2_2B") (pintype "passive"))
      (node (ref "R29") (pin "1") (pinfunction "1_1") (pintype "passive"))
      (node (ref "U1") (pin "33") (pinfunction "SDA/IO21_33") (pintype "bidirectional"))
      (node (ref "U6") (pin "8") (pinfunction "SDA_8") (pintype "input"))
    )
    (net (code "37") (name "ESP32_TXD0") (class "Default")
      (node (ref "J7") (pin "2") (pinfunction "2_2") (pintype "passive"))
      (node (ref "J8") (pin "2") (pinfunction "2_2") (pintype "passive"))
      (node (ref "LED_TX") (pin "1") (pinfunction "1_1") (pintype "passive"))
      (node (ref "U1") (pin "35") (pinfunction "TX-IO1_35") (pintype "bidirectional"))
      (node (ref "U2") (pin "3") (pinfunction "RXI_3") (pintype "bidirectional"))
    )
    (net (code "38") (name "GND") (class "Default")
      (node (ref "C1") (pin "2") (pinfunction "2_2") (pintype "passive"))
      (node (ref "C10") (pin "-") (pinfunction "-_-") (pintype "passive"))
      (node (ref "C11") (pin "2") (pinfunction "2_2") (pintype "passive"))
      (node (ref "C12") (pin "2") (pinfunction "2_2") (pintype "passive"))
      (node (ref "C13") (pin "2") (pinfunction "2_2") (pintype "passive"))
      (node (ref "C14") (pin "2") (pinfunction "2_2") (pintype "passive"))
      (node (ref "C15") (pin "2") (pinfunction "2_2") (pintype "passive"))
      (node (ref "C16") (pin "2") (pinfunction "2_2") (pintype "passive"))
      (node (ref "C17") (pin "2") (pinfunction "2_2") (pintype "passive"))
      (node (ref "C18") (pin "2") (pinfunction "2_2") (pintype "passive"))
      (node (ref "C19") (pin "2") (pinfunction "2_2") (pintype "passive"))
      (node (ref "C2") (pin "2") (pinfunction "2_2") (pintype "passive"))
      (node (ref "C3") (pin "2") (pinfunction "2_2") (pintype "passive"))
      (node (ref "C4") (pin "2") (pinfunction "2_2") (pintype "passive"))
      (node (ref "C5") (pin "2") (pinfunction "2_2") (pintype "passive"))
      (node (ref "C6") (pin "-") (pinfunction "-_-") (pintype "passive"))
      (node (ref "C7") (pin "2") (pinfunction "2_2") (pintype "passive"))
      (node (ref "C8") (pin "2") (pinfunction "2_2") (pintype "passive"))
      (node (ref "C9") (pin "-") (pinfunction "-_-") (pintype "passive"))
      (node (ref "D7") (pin "GND") (pinfunction "GND_GND") (pintype "bidirectional"))
      (node (ref "DOOT") (pin "1") (pinfunction "1_1") (pintype "passive"))
      (node (ref "DOOT") (pin "2") (pinfunction "1_2") (pintype "passive"))
      (node (ref "J1") (pin "GND") (pinfunction "GNDBREAK_GND") (pintype "bidirectional"))
      (node (ref "J10") (pin "6") (pinfunction "6_6") (pintype "passive"))
      (node (ref "J10") (pin "7") (pinfunction "7_7") (pintype "passive"))
      (node (ref "J13") (pin "1") (pinfunction "1_1") (pintype "power_in"))
      (node (ref "J15") (pin "10") (pinfunction "GND_10") (pintype "bidirectional"))
      (node (ref "J15") (pin "11") (pinfunction "GND_11") (pintype "bidirectional"))
      (node (ref "J15") (pin "12") (pinfunction "GND_12") (pintype "bidirectional"))
      (node (ref "J15") (pin "13") (pinfunction "GND_13") (pintype "bidirectional"))
      (node (ref "J15") (pin "6") (pinfunction "GND_6") (pintype "bidirectional"))
      (node (ref "J16") (pin "2") (pinfunction "2_2") (pintype "passive"))
      (node (ref "J2") (pin "GND") (pinfunction "GND_GND") (pintype "bidirectional"))
      (node (ref "J2") (pin "GND2") (pinfunction "GND_GND2") (pintype "bidirectional"))
      (node (ref "J3") (pin "GND") (pinfunction "4_GND") (pintype "passive"))
      (node (ref "J4") (pin "3") (pinfunction "3_3") (pintype "passive"))
      (node (ref "J4") (pin "5") (pinfunction "5_5") (pintype "passive"))
      (node (ref "J4") (pin "7") (pinfunction "7_7") (pintype "passive"))
      (node (ref "J4") (pin "9") (pinfunction "9_9") (pintype "passive"))
      (node (ref "J5") (pin "4") (pinfunction "4_4") (pintype "passive"))
      (node (ref "J6") (pin "4A") (pinfunction "4_4A") (pintype "passive"))
      (node (ref "J6") (pin "4B") (pinfunction "4_4B") (pintype "passive"))
      (node (ref "J9") (pin "6") (pinfunction "6_6") (pintype "passive"))
      (node (ref "J9") (pin "7") (pinfunction "7_7") (pintype "passive"))
      (node (ref "JP2") (pin "1") (pinfunction "2_1") (pintype "passive"))
      (node (ref "LED_18") (pin "1") (pinfunction "1_1") (pintype "passive"))
      (node (ref "LED_PWR") (pin "1") (pinfunction "1_1") (pintype "passive"))
      (node (ref "Q2") (pin "1") (pinfunction "E_1") (pintype "passive"))
      (node (ref "Q2") (pin "4") (pinfunction "E_4") (pintype "passive"))
      (node (ref "R11") (pin "1") (pinfunction "1_1") (pintype "passive"))
      (node (ref "R15") (pin "1") (pinfunction "1_1") (pintype "passive"))
      (node (ref "R16") (pin "1") (pinfunction "1_1") (pintype "passive"))
      (node (ref "R17") (pin "1") (pinfunction "1_1") (pintype "passive"))
      (node (ref "R18") (pin "1") (pinfunction "1_1") (pintype "passive"))
      (node (ref "R19") (pin "1") (pinfunction "1_1") (pintype "passive"))
      (node (ref "R2") (pin "1") (pinfunction "1_1") (pintype "passive"))
      (node (ref "R20") (pin "1") (pinfunction "1_1") (pintype "passive"))
      (node (ref "R22") (pin "1") (pinfunction "1_1") (pintype "passive"))
      (node (ref "R24") (pin "1") (pinfunction "1_1") (pintype "passive"))
      (node (ref "R25") (pin "1") (pinfunction "1_1") (pintype "passive"))
      (node (ref "R26") (pin "1") (pinfunction "1_1") (pintype "passive"))
      (node (ref "R27") (pin "1") (pinfunction "1_1") (pintype "passive"))
      (node (ref "R3") (pin "1") (pinfunction "1_1") (pintype "passive"))
      (node (ref "S1") (pin "1") (pinfunction "1_1") (pintype "passive"))
      (node (ref "S1") (pin "2") (pinfunction "1_2") (pintype "passive"))
      (node (ref "SHLD") (pin "1") (pinfunction "1_1") (pintype "passive"))
      (node (ref "U1") (pin "1") (pinfunction "GND_1") (pintype "bidirectional"))
      (node (ref "U1") (pin "15") (pinfunction "GND_15") (pintype "bidirectional"))
      (node (ref "U1") (pin "38") (pinfunction "GND_38") (pintype "bidirectional"))
      (node (ref "U1") (pin "GND") (pinfunction "GND_GND") (pintype "bidirectional"))
      (node (ref "U1") (pin "GNDT1") (pinfunction "GND_GNDT1") (pintype "bidirectional"))
      (node (ref "U1") (pin "GNDT2") (pinfunction "GND_GNDT2") (pintype "bidirectional"))
      (node (ref "U1") (pin "GNDT3") (pinfunction "GND_GNDT3") (pintype "bidirectional"))
      (node (ref "U1") (pin "GNDT4") (pinfunction "GND_GNDT4") (pintype "bidirectional"))
      (node (ref "U1") (pin "GNDT5") (pinfunction "GND_GNDT5") (pintype "bidirectional"))
      (node (ref "U1") (pin "GNDT6") (pinfunction "GND_GNDT6") (pintype "bidirectional"))
      (node (ref "U1") (pin "GNDT7") (pinfunction "GND_GNDT7") (pintype "bidirectional"))
      (node (ref "U1") (pin "GNDT8") (pinfunction "GND_GNDT8") (pintype "bidirectional"))
      (node (ref "U2") (pin "1") (pinfunction "GND_1") (pintype "bidirectional"))
      (node (ref "U4") (pin "2") (pinfunction "GND_2") (pintype "input"))
      (node (ref "U5") (pin "2") (pinfunction "VSS_2") (pintype "power_in"))
      (node (ref "U6") (pin "1") (pinfunction "CTG_1") (pintype "input"))
      (node (ref "U6") (pin "4") (pinfunction "GND_4") (pintype "bidirectional"))
      (node (ref "U6") (pin "6") (pinfunction "QSTRT_6") (pintype "bidirectional"))
      (node (ref "U6") (pin "9") (pinfunction "GND_9") (pintype "bidirectional"))
    )
    (net (code "39") (name "LED_DO") (class "Default")
      (node (ref "J10") (pin "1") (pinfunction "1_1") (pintype "passive"))
      (node (ref "J9") (pin "1") (pinfunction "1_1") (pintype "passive"))
      (node (ref "JP10") (pin "2") (pinfunction "2_2") (pintype "passive"))
    )
    (net (code "40") (name "Net-(BYP-Pad1)") (class "Default")
      (node (ref "BYP") (pin "1") (pinfunction "1_1") (pintype "passive"))
      (node (ref "C4") (pin "1") (pinfunction "1_1") (pintype "passive"))
      (node (ref "F1") (pin "1") (pinfunction "1_1") (pintype "bidirectional"))
      (node (ref "MEAS") (pin "2") (pinfunction "2_2") (pintype "passive"))
      (node (ref "MEAS") (pin "4") (pinfunction "2_4") (pintype "passive"))
    )
    (net (code "41") (name "Net-(D2-PadC)") (class "Default")
      (node (ref "D2") (pin "C") (pinfunction "C_C") (pintype "passive"))
      (node (ref "R4") (pin "2") (pinfunction "2_2") (pintype "passive"))
    )
    (net (code "42") (name "Net-(D3-PadC)") (class "Default")
      (node (ref "D3") (pin "C") (pinfunction "C_C") (pintype "passive"))
      (node (ref "R5") (pin "2") (pinfunction "2_2") (pintype "passive"))
    )
    (net (code "43") (name "Net-(D4-PadC)") (class "Default")
      (node (ref "D4") (pin "C") (pinfunction "C_C") (pintype "passive"))
      (node (ref "R21") (pin "1") (pinfunction "1_1") (pintype "passive"))
    )
    (net (code "44") (name "Net-(D5-PadC)") (class "Default")
      (node (ref "D5") (pin "C") (pinfunction "C_C") (pintype "passive"))
      (node (ref "R8") (pin "2") (pinfunction "2_2") (pintype "passive"))
    )
    (net (code "45") (name "Net-(D6-PadC)") (class "Default")
      (node (ref "D6") (pin "C") (pinfunction "C_C") (pintype "passive"))
      (node (ref "R9") (pin "2") (pinfunction "2_2") (pintype "passive"))
    )
    (net (code "46") (name "Net-(D7-PadDO)") (class "Default")
      (node (ref "D7") (pin "DO") (pinfunction "DO_DO") (pintype "bidirectional"))
      (node (ref "JP10") (pin "1") (pinfunction "1_1") (pintype "passive"))
    )
    (net (code "47") (name "Net-(I2C-Pad1)") (class "Default")
      (node (ref "I2C") (pin "1") (pinfunction "1_1") (pintype "passive"))
      (node (ref "R29") (pin "2") (pinfunction "2_2") (pintype "passive"))
    )
    (net (code "48") (name "Net-(I2C-Pad3)") (class "Default")
      (node (ref "I2C") (pin "3") (pinfunction "3_3") (pintype "passive"))
      (node (ref "R28") (pin "2") (pinfunction "2_2") (pintype "passive"))
    )
    (net (code "49") (name "Net-(J1-PWR)") (class "Default")
      (node (ref "D1") (pin "A") (pinfunction "A_A") (pintype "passive"))
      (node (ref "J1") (pin "VIN0") (pinfunction "PWR_VIN0") (pintype "bidirectional"))
    )
    (net (code "50") (name "Net-(J2-CC1)") (class "Default")
      (node (ref "J2") (pin "A5") (pinfunction "CC1_A5") (pintype "bidirectional"))
      (node (ref "R3") (pin "2") (pinfunction "2_2") (pintype "passive"))
    )
    (net (code "51") (name "Net-(J2-CC2)") (class "Default")
      (node (ref "J2") (pin "B5") (pinfunction "CC2_B5") (pintype "bidirectional"))
      (node (ref "R2") (pin "2") (pinfunction "2_2") (pintype "passive"))
    )
    (net (code "52") (name "Net-(J2-SHLD-PadSHLD1)") (class "Default")
      (node (ref "J2") (pin "SHLD1") (pinfunction "SHLD_SHLD1") (pintype "bidirectional"))
      (node (ref "J2") (pin "SHLD2") (pinfunction "SHLD_SHLD2") (pintype "bidirectional"))
      (node (ref "J2") (pin "SHLD3") (pinfunction "SHLD_SHLD3") (pintype "bidirectional"))
      (node (ref "J2") (pin "SHLD4") (pinfunction "SHLD_SHLD4") (pintype "bidirectional"))
      (node (ref "J2") (pin "SHLD5") (pinfunction "SHLD_SHLD5") (pintype "bidirectional"))
      (node (ref "J2") (pin "SHLD6") (pinfunction "SHLD_SHLD6") (pintype "bidirectional"))
      (node (ref "J2") (pin "SHLD7") (pinfunction "SHLD_SHLD7") (pintype "bidirectional"))
      (node (ref "J2") (pin "SHLD8") (pinfunction "SHLD_SHLD8") (pintype "bidirectional"))
      (node (ref "SHLD") (pin "2") (pinfunction "2_2") (pintype "passive"))
    )
    (net (code "53") (name "Net-(J3-2)") (class "Default")
      (node (ref "J2") (pin "A7") (pinfunction "D-_A7") (pintype "bidirectional"))
      (node (ref "J2") (pin "B7") (pinfunction "D-_B7") (pintype "bidirectional"))
      (node (ref "J3") (pin "D-") (pinfunction "2_D-") (pintype "passive"))
      (node (ref "U2") (pin "6") (pinfunction "UD-_6") (pintype "bidirectional"))
    )
    (net (code "54") (name "Net-(J3-3)") (class "Default")
      (node (ref "J2") (pin "A6") (pinfunction "D+_A6") (pintype "bidirectional"))
      (node (ref "J2") (pin "B6") (pinfunction "D+_B6") (pintype "bidirectional"))
      (node (ref "J3") (pin "D+") (pinfunction "3_D+") (pintype "passive"))
      (node (ref "U2") (pin "5") (pinfunction "UD+_5") (pintype "bidirectional"))
    )
    (net (code "55") (name "Net-(J15-DET)") (class "Default")
      (node (ref "J15") (pin "9") (pinfunction "DET_9") (pintype "bidirectional"))
      (node (ref "SD_DET") (pin "1") (pinfunction "1_1") (pintype "passive"))
    )
    (net (code "56") (name "Net-(LED_18-Pad2)") (class "Default")
      (node (ref "LED_18") (pin "2") (pinfunction "2_2") (pintype "passive"))
      (node (ref "R9") (pin "1") (pinfunction "1_1") (pintype "passive"))
    )
    (net (code "57") (name "Net-(LED_CHG-Pad1)") (class "Default")
      (node (ref "LED_CHG") (pin "1") (pinfunction "1_1") (pintype "passive"))
      (node (ref "R21") (pin "2") (pinfunction "2_2") (pintype "passive"))
    )
    (net (code "58") (name "Net-(LED_PWR-Pad2)") (class "Default")
      (node (ref "LED_PWR") (pin "2") (pinfunction "2_2") (pintype "passive"))
      (node (ref "R8") (pin "1") (pinfunction "1_1") (pintype "passive"))
    )
    (net (code "59") (name "Net-(LED_RX-Pad2)") (class "Default")
      (node (ref "LED_RX") (pin "2") (pinfunction "2_2") (pintype "passive"))
      (node (ref "R5") (pin "1") (pinfunction "1_1") (pintype "passive"))
    )
    (net (code "60") (name "Net-(LED_TX-Pad2)") (class "Default")
      (node (ref "LED_TX") (pin "2") (pinfunction "2_2") (pintype "passive"))
      (node (ref "R4") (pin "1") (pinfunction "1_1") (pintype "passive"))
    )
    (net (code "61") (name "Net-(Q1A-B)") (class "Default")
      (node (ref "Q1") (pin "5") (pinfunction "B_5") (pintype "passive"))
      (node (ref "R7") (pin "2") (pinfunction "2_2") (pintype "passive"))
    )
    (net (code "62") (name "Net-(Q1B-B)") (class "Default")
      (node (ref "Q1") (pin "2") (pinfunction "B_2") (pintype "passive"))
      (node (ref "R6") (pin "2") (pinfunction "2_2") (pintype "passive"))
    )
    (net (code "63") (name "Net-(Q2A-B)") (class "Default")
      (node (ref "Q2") (pin "5") (pinfunction "B_5") (pintype "passive"))
      (node (ref "Q2") (pin "6") (pinfunction "C_6") (pintype "passive"))
      (node (ref "R13") (pin "1") (pinfunction "1_1") (pintype "passive"))
    )
    (net (code "64") (name "Net-(Q2A-C)") (class "Default")
      (node (ref "Q2") (pin "3") (pinfunction "C_3") (pintype "passive"))
      (node (ref "R30") (pin "1") (pinfunction "1_1") (pintype "passive"))
    )
    (net (code "65") (name "Net-(Q2B-B)") (class "Default")
      (node (ref "Q2") (pin "2") (pinfunction "B_2") (pintype "passive"))
      (node (ref "R12") (pin "2") (pinfunction "2_2") (pintype "passive"))
    )
    (net (code "66") (name "Net-(Q3-D)") (class "Default")
      (node (ref "Q3") (pin "3") (pinfunction "D_3") (pintype "bidirectional"))
      (node (ref "Q4") (pin "1") (pinfunction "E_1") (pintype "passive"))
      (node (ref "Q5") (pin "3") (pinfunction "D_3") (pintype "bidirectional"))
    )
    (net (code "67") (name "Net-(Q3-G)") (class "Default")
      (node (ref "Q3") (pin "1") (pinfunction "G_1") (pintype "bidirectional"))
      (node (ref "R14") (pin "2") (pinfunction "2_2") (pintype "passive"))
      (node (ref "R30") (pin "2") (pinfunction "2_2") (pintype "passive"))
    )
    (net (code "68") (name "Net-(Q4A-B)") (class "Default")
      (node (ref "Q4") (pin "2") (pinfunction "B_2") (pintype "passive"))
      (node (ref "Q4") (pin "5") (pinfunction "B_5") (pintype "passive"))
      (node (ref "Q4") (pin "6") (pinfunction "C_6") (pintype "passive"))
      (node (ref "R15") (pin "2") (pinfunction "2_2") (pintype "passive"))
    )
    (net (code "69") (name "Net-(Q4B-C)") (class "Default")
      (node (ref "Q4") (pin "3") (pinfunction "C_3") (pintype "passive"))
      (node (ref "Q5") (pin "1") (pinfunction "G_1") (pintype "bidirectional"))
      (node (ref "R16") (pin "2") (pinfunction "2_2") (pintype "passive"))
    )
    (net (code "70") (name "Net-(Q6A-B)") (class "Default")
      (node (ref "Q6") (pin "2") (pinfunction "B_2") (pintype "passive"))
      (node (ref "Q6") (pin "5") (pinfunction "B_5") (pintype "passive"))
      (node (ref "Q6") (pin "6") (pinfunction "C_6") (pintype "passive"))
      (node (ref "R17") (pin "2") (pinfunction "2_2") (pintype "passive"))
    )
    (net (code "71") (name "Net-(Q6B-C)") (class "Default")
      (node (ref "Q6") (pin "3") (pinfunction "C_3") (pintype "passive"))
      (node (ref "Q7") (pin "1") (pinfunction "G_1") (pintype "bidirectional"))
      (node (ref "R18") (pin "2") (pinfunction "2_2") (pintype "passive"))
    )
    (net (code "72") (name "Net-(Q8A-B)") (class "Default")
      (node (ref "Q8") (pin "2") (pinfunction "B_2") (pintype "passive"))
      (node (ref "Q8") (pin "5") (pinfunction "B_5") (pintype "passive"))
      (node (ref "Q8") (pin "6") (pinfunction "C_6") (pintype "passive"))
      (node (ref "R19") (pin "2") (pinfunction "2_2") (pintype "passive"))
    )
    (net (code "73") (name "Net-(Q8B-C)") (class "Default")
      (node (ref "Q8") (pin "3") (pinfunction "C_3") (pintype "passive"))
      (node (ref "Q9") (pin "1") (pinfunction "G_1") (pintype "bidirectional"))
      (node (ref "R20") (pin "2") (pinfunction "2_2") (pintype "passive"))
    )
    (net (code "74") (name "Net-(Q10A-B)") (class "Default")
      (node (ref "Q10") (pin "2") (pinfunction "B_2") (pintype "passive"))
      (node (ref "Q10") (pin "5") (pinfunction "B_5") (pintype "passive"))
      (node (ref "Q10") (pin "6") (pinfunction "C_6") (pintype "passive"))
      (node (ref "R24") (pin "2") (pinfunction "2_2") (pintype "passive"))
    )
    (net (code "75") (name "Net-(Q10B-C)") (class "Default")
      (node (ref "Q10") (pin "3") (pinfunction "C_3") (pintype "passive"))
      (node (ref "Q11") (pin "1") (pinfunction "G_1") (pintype "bidirectional"))
      (node (ref "R25") (pin "2") (pinfunction "2_2") (pintype "passive"))
    )
    (net (code "76") (name "Net-(Q12A-B)") (class "Default")
      (node (ref "Q12") (pin "2") (pinfunction "B_2") (pintype "passive"))
      (node (ref "Q12") (pin "5") (pinfunction "B_5") (pintype "passive"))
      (node (ref "Q12") (pin "6") (pinfunction "C_6") (pintype "passive"))
      (node (ref "R26") (pin "2") (pinfunction "2_2") (pintype "passive"))
    )
    (net (code "77") (name "Net-(Q12B-C)") (class "Default")
      (node (ref "Q12") (pin "3") (pinfunction "C_3") (pintype "passive"))
      (node (ref "Q13") (pin "1") (pinfunction "G_1") (pintype "bidirectional"))
      (node (ref "R27") (pin "2") (pinfunction "2_2") (pintype "passive"))
    )
    (net (code "78") (name "Net-(U2-V3)") (class "Default")
      (node (ref "C8") (pin "1") (pinfunction "1_1") (pintype "passive"))
      (node (ref "U2") (pin "4") (pinfunction "V3_4") (pintype "bidirectional"))
    )
    (net (code "79") (name "Net-(U3-ADJ)") (class "Default")
      (node (ref "R10") (pin "1") (pinfunction "1_1") (pintype "passive"))
      (node (ref "R11") (pin "2") (pinfunction "2_2") (pintype "passive"))
      (node (ref "U3") (pin "1") (pinfunction "ADJ_1") (pintype "input"))
    )
    (net (code "80") (name "Net-(U5-PROG)") (class "Default")
      (node (ref "R22") (pin "2") (pinfunction "2_2") (pintype "passive"))
      (node (ref "U5") (pin "5") (pinfunction "PROG_5") (pintype "input"))
    )
    (net (code "81") (name "Net-(U5-STAT)") (class "Default")
      (node (ref "LED_CHG") (pin "2") (pinfunction "2_2") (pintype "passive"))
      (node (ref "U5") (pin "1") (pinfunction "STAT_1") (pintype "output"))
    )
    (net (code "82") (name "VIN") (class "Default")
      (node (ref "C9") (pin "+") (pinfunction "+_+") (pintype "passive"))
      (node (ref "D1") (pin "C") (pinfunction "C_C") (pintype "passive"))
      (node (ref "J10") (pin "8") (pinfunction "8_8") (pintype "passive"))
      (node (ref "J9") (pin "8") (pinfunction "8_8") (pintype "passive"))
      (node (ref "U3") (pin "3") (pinfunction "IN_3") (pintype "input"))
    )
    (net (code "83") (name "V_BATT") (class "Default")
      (node (ref "C16") (pin "1") (pinfunction "1_1") (pintype "passive"))
      (node (ref "C17") (pin "1") (pinfunction "1_1") (pintype "passive"))
      (node (ref "J16") (pin "1") (pinfunction "1_1") (pintype "passive"))
      (node (ref "JP2") (pin "2") (pinfunction "1_2") (pintype "passive"))
      (node (ref "Q8") (pin "1") (pinfunction "E_1") (pintype "passive"))
      (node (ref "Q9") (pin "3") (pinfunction "D_3") (pintype "bidirectional"))
      (node (ref "U5") (pin "3") (pinfunction "VBAT_3") (pintype "power_in"))
      (node (ref "U6") (pin "2") (pinfunction "CELL_2") (pintype "input"))
      (node (ref "U6") (pin "3") (pinfunction "VDD_3") (pintype "bidirectional"))
    )
    (net (code "84") (name "V_USB") (class "Default")
      (node (ref "C5") (pin "1") (pinfunction "1_1") (pintype "passive"))
      (node (ref "C6") (pin "+") (pinfunction "+_+") (pintype "passive"))
      (node (ref "J2") (pin "VBUS1") (pinfunction "VBUS_VBUS1") (pintype "bidirectional"))
      (node (ref "J2") (pin "VBUS2") (pinfunction "VBUS_VBUS2") (pintype "bidirectional"))
      (node (ref "J3") (pin "VBUS") (pinfunction "1_VBUS") (pintype "passive"))
      (node (ref "Q10") (pin "1") (pinfunction "E_1") (pintype "passive"))
      (node (ref "Q11") (pin "3") (pinfunction "D_3") (pintype "bidirectional"))
      (node (ref "Q3") (pin "2") (pinfunction "S_2") (pintype "bidirectional"))
      (node (ref "R13") (pin "2") (pinfunction "2_2") (pintype "passive"))
      (node (ref "R14") (pin "1") (pinfunction "1_1") (pintype "passive"))
    )
    (net (code "85") (name "unconnected-(J1-GND-PadP$4)") (class "Default")
      (node (ref "J1") (pin "P$4") (pinfunction "GND_P$4") (pintype "bidirectional"))
    )
    (net (code "86") (name "unconnected-(J4-Pad1)") (class "Default")
      (node (ref "J4") (pin "1") (pinfunction "1_1") (pintype "passive"))
    )
    (net (code "87") (name "unconnected-(J4-Pad10)") (class "Default")
      (node (ref "J4") (pin "10") (pinfunction "10_10") (pintype "passive"))
    )
    (net (code "88") (name "unconnected-(J15-DAT1-Pad8)") (class "Default")
      (node (ref "J15") (pin "8") (pinfunction "DAT1_8") (pintype "bidirectional"))
    )
    (net (code "89") (name "unconnected-(J15-DAT2-Pad1)") (class "Default")
      (node (ref "J15") (pin "1") (pinfunction "DAT2_1") (pintype "bidirectional"))
    )
    (net (code "90") (name "unconnected-(U2-R232-Pad15)") (class "Default")
      (node (ref "U2") (pin "15") (pinfunction "R232_15") (pintype "bidirectional"))
    )
    (net (code "91") (name "unconnected-(U2-~{CTS}-Pad9)") (class "Default")
      (node (ref "U2") (pin "9") (pinfunction "~{CTS}_9") (pintype "bidirectional"))
    )
    (net (code "92") (name "unconnected-(U2-~{DCD}-Pad12)") (class "Default")
      (node (ref "U2") (pin "12") (pinfunction "~{DCD}_12") (pintype "bidirectional"))
    )
    (net (code "93") (name "unconnected-(U2-~{DSR}-Pad10)") (class "Default")
      (node (ref "U2") (pin "10") (pinfunction "~{DSR}_10") (pintype "bidirectional"))
    )
    (net (code "94") (name "unconnected-(U2-~{RI}-Pad11)") (class "Default")
      (node (ref "U2") (pin "11") (pinfunction "~{RI}_11") (pintype "bidirectional"))
    )
  )
)
